# pcb.net
KiCad netlist of a schematic drawn in EAGLE
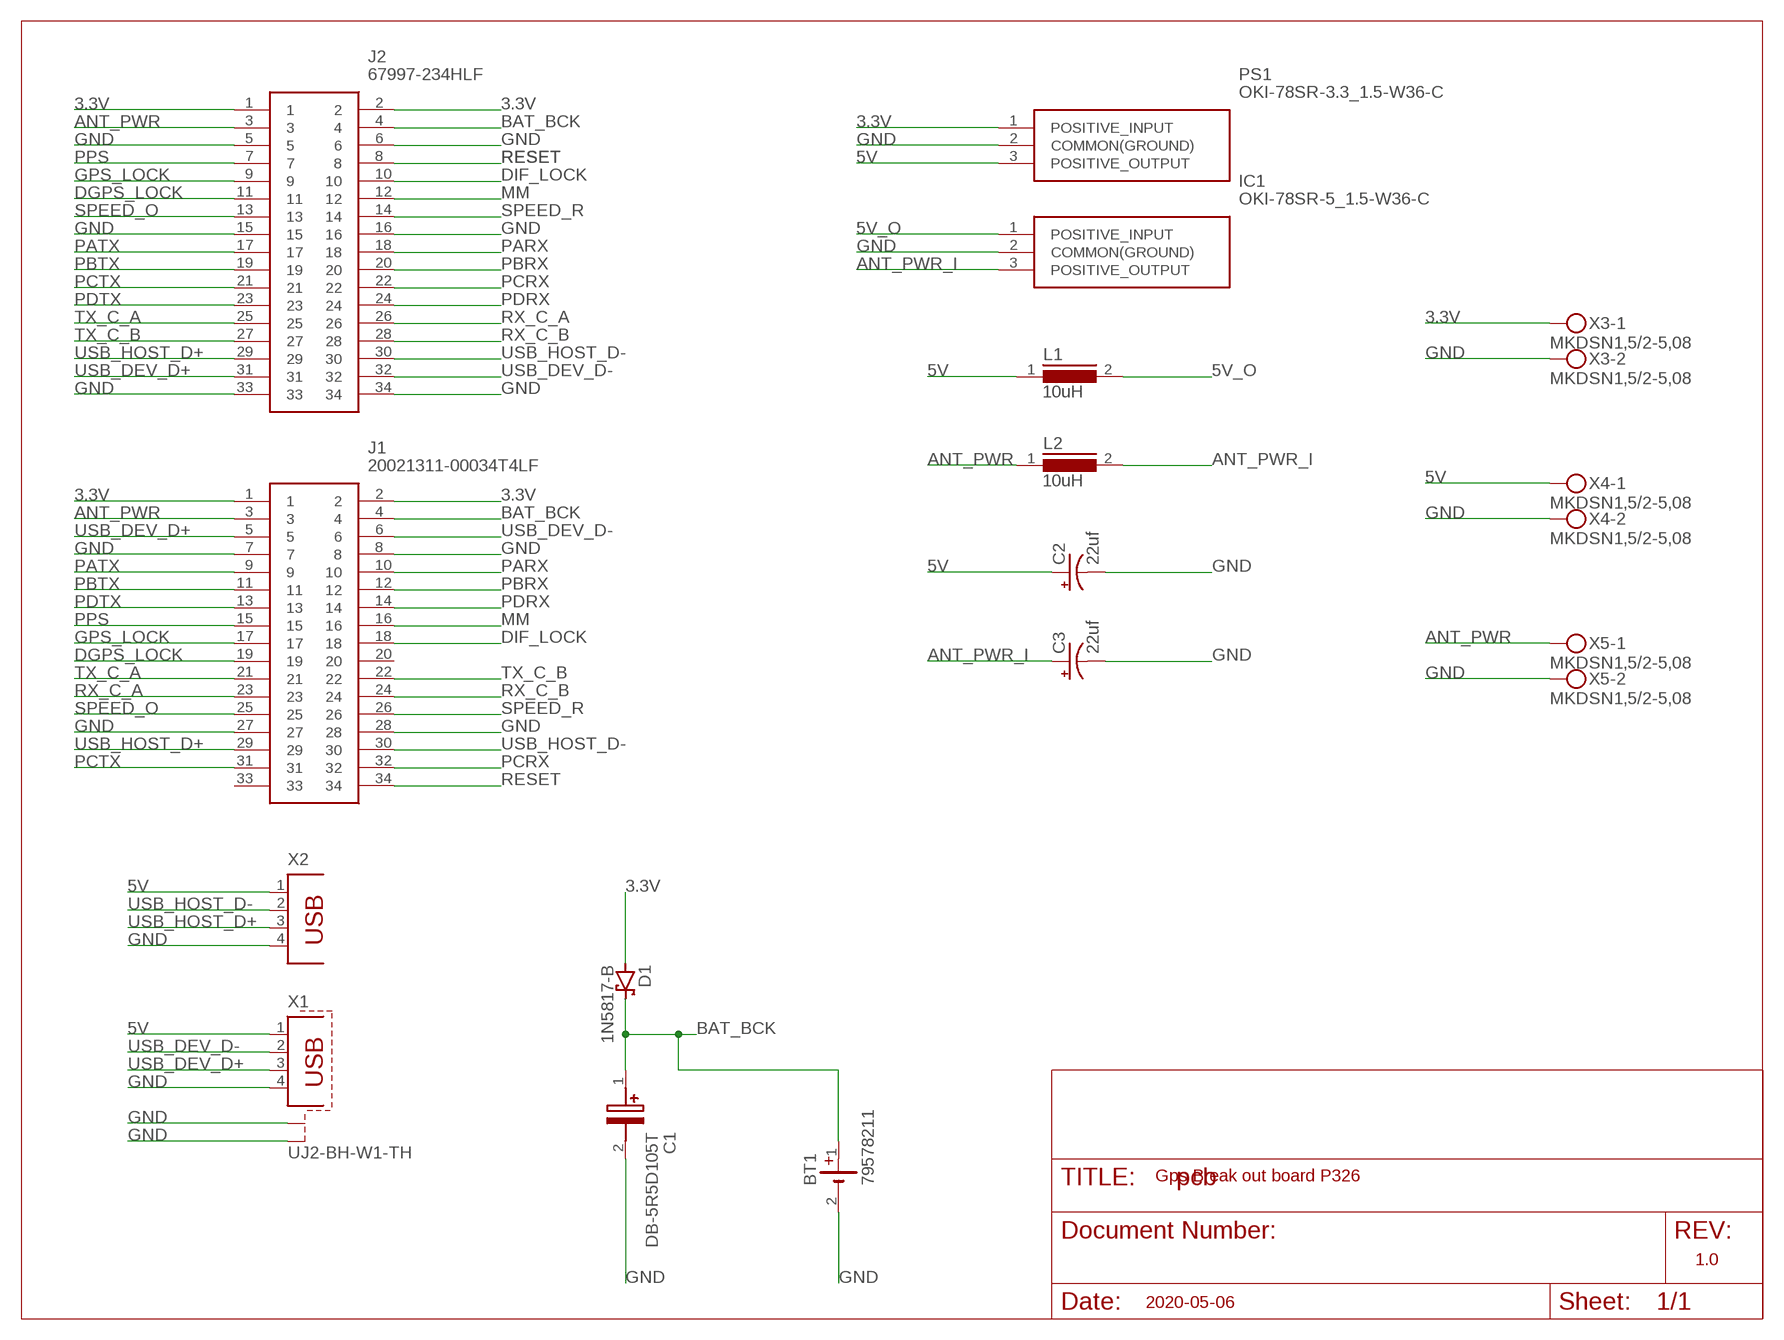
[diagram p0: schematic, sheet 1]

(export (version "E")
  (design (tool "Eeschema 10.0.6"))
  (components
    (comp (ref "BT1")
      (value "79578211")
      (footprint "eagle-import:79578211")
      (fields
        (field (name "DIGIKEY_PART_NO") "732-12330-ND")
        (field (name "MANUFACTURER") "Wurth Electronics Inc.")
        (field (name "CREATED_BY") "PCBLayout.com")
      )
      (libsource (lib "eagle-import") (part "79578211"))
    )
    (comp (ref "C1")
      (value "DB-5R5D105T")
      (footprint "eagle-import:CAPPRD500W130D2150H800")
      (fields (field (name "MOUSER_PART_NUMBER") "555-DB-5R5D105T"))
      (libsource (lib "eagle-import") (part "DB-5R5D105T"))
    )
    (comp (ref "C2")
      (value "22uf")
      (footprint "eagle-import:CAPPRD508W65D1000H1100B")
      (libsource (lib "eagle-import") (part "C-POL-USRADIAL-11MM-DIA_"))
    )
    (comp (ref "C3")
      (value "22uf")
      (footprint "eagle-import:CAPPRD508W65D1000H1100B")
      (libsource (lib "eagle-import") (part "C-POL-USRADIAL-11MM-DIA_"))
    )
    (comp (ref "D1")
      (value "1N5817-B")
      (footprint "eagle-import:DO41-7.6")
      (libsource (lib "eagle-import") (part "1N5817-B"))
    )
    (comp (ref "IC1")
      (value "OKI-78SR-5_1.5-W36-C")
      (footprint "eagle-import:OKI-78SR")
      (fields
        (field (name "MANUFACTURER_PART_NUMBER") "OKI-78SR-5/1.5-W36-C")
        (field (name "MOUSER_PART_NUMBER") "580-OKI78SR5/1.5W36C")
        (field (name "RS_PART_NUMBER") "7962132P")
      )
      (libsource (lib "eagle-import") (part "OKI-78SR-5_1.5-W36-C"))
    )
    (comp (ref "J1")
      (value "20021311-00034T4LF")
      (footprint "eagle-import:SFMC11701LDK")
      (fields
        (field (name "MANUFACTURER_PART_NUMBER") "SFMC-117-01-L-D-K")
        (field (name "MOUSER_PART_NUMBER") "200-SFMC11701LDK")
        (field (name "MANUFACTURER_NAME") "Amphenol ICC (FCI)")
        (field (name "MANUFACTURER_PART_NUMBER_1") "20021311-00034T4LF")
        (field (name "MOUSER_PART_NUMBER_1") "649-221311-00034T4LF")
        (field (name "MOUSER_PRICE-STOCK") "https://www.mouser.ca/ProductDetail/Amphenol-FCI/20021311-00034T4LF?qs=%2Fha2pyFaduhY7txd7xCZH4MnoZVHG9D20IyDq2KsCOnVLlItFYWmroWGFWusbTUh")
      )
      (libsource (lib "eagle-import") (part "SFMC-117-01-L-D-K"))
    )
    (comp (ref "J2")
      (value "67997-234HLF")
      (footprint "eagle-import:HDRV34W64P254_2X17_4318X495X83")
      (fields
        (field (name "MANUFACTURER_PART_NUMBER") "TSW-117-07-L-D")
        (field (name "MOUSER_PART_NUMBER") "200-TSW11707LD")
        (field (name "RS_PART_NUMBER") "1802714P")
        (field (name "MANUFACTURER_NAME") "Amphenol ICC (FCI)")
        (field (name "MANUFACTURER_PART_NUMBER_1") "67997-234HLF")
        (field (name "MOUSER_PART_NUMBER_1") "649-67997-234HLF")
        (field (name "MOUSER_PRICE-STOCK") "https://www.mouser.ca/ProductDetail/Amphenol-FCI/67997-234HLF?qs=%2Fha2pyFaduho4QXapRmeXGuJyHmXXipd3LGGQJh2eTsVKLqIuO2D5A%3D%3D")
      )
      (libsource (lib "eagle-import") (part "TSW-117-07-L-D"))
    )
    (comp (ref "L1")
      (value "10uH")
      (footprint "eagle-import:82114R")
      (libsource (lib "eagle-import") (part "82114R"))
    )
    (comp (ref "L2")
      (value "10uH")
      (footprint "eagle-import:82114R")
      (libsource (lib "eagle-import") (part "82114R"))
    )
    (comp (ref "PS1")
      (value "OKI-78SR-3.3_1.5-W36-C")
      (footprint "eagle-import:OKI-78SR")
      (fields
        (field (name "MANUFACTURER_PART_NUMBER") "OKI-78SR-5/1.5-W36-C")
        (field (name "MOUSER_PART_NUMBER") "580-OKI78SR5/1.5W36C")
        (field (name "RS_PART_NUMBER") "7962132P")
      )
      (libsource (lib "eagle-import") (part "OKI-78SR-5_1.5-W36-C"))
    )
    (comp (ref "X1")
      (value "UJ2-BH-W1-TH")
      (footprint "eagle-import:PN61729-S")
      (libsource (lib "eagle-import") (part "PN61729-S"))
    )
    (comp (ref "X2")
      (value "PN87520")
      (footprint "eagle-import:PN87520")
      (libsource (lib "eagle-import") (part "PN87520"))
    )
    (comp (ref "X3")
      (value "MKDSN1,5/2-5,08")
      (footprint "eagle-import:MKDSN1,5_2-5,08")
      (libsource (lib "eagle-import") (part "MKDSN1,5/2-5,08"))
    )
    (comp (ref "X4")
      (value "MKDSN1,5/2-5,08")
      (footprint "eagle-import:MKDSN1,5_2-5,08")
      (libsource (lib "eagle-import") (part "MKDSN1,5/2-5,08"))
    )
    (comp (ref "X5")
      (value "MKDSN1,5/2-5,08")
      (footprint "eagle-import:MKDSN1,5_2-5,08")
      (libsource (lib "eagle-import") (part "MKDSN1,5/2-5,08"))
    )
  )
  (nets
    (net (code "1") (name "/3.3V") (class "Default")
      (node (ref "D1") (pin "A") (pinfunction "A_A") (pintype "passive"))
      (node (ref "J1") (pin "1") (pinfunction "1_1") (pintype "bidirectional"))
      (node (ref "J1") (pin "2") (pinfunction "2_2") (pintype "bidirectional"))
      (node (ref "J2") (pin "1") (pinfunction "1_1") (pintype "bidirectional"))
      (node (ref "J2") (pin "2") (pinfunction "2_2") (pintype "bidirectional"))
      (node (ref "PS1") (pin "1") (pinfunction "POSITIVE_INPUT_1") (pintype "bidirectional"))
      (node (ref "X3") (pin "1") (pinfunction "KL_1") (pintype "passive"))
    )
    (net (code "2") (name "/5V") (class "Default")
      (node (ref "C2") (pin "1") (pinfunction "+_1") (pintype "passive"))
      (node (ref "L1") (pin "1") (pinfunction "1_1") (pintype "passive"))
      (node (ref "PS1") (pin "3") (pinfunction "POSITIVE_OUTPUT_3") (pintype "bidirectional"))
      (node (ref "X1") (pin "1") (pinfunction "1_1") (pintype "passive"))
      (node (ref "X2") (pin "1") (pinfunction "1_1") (pintype "passive"))
      (node (ref "X4") (pin "1") (pinfunction "KL_1") (pintype "passive"))
    )
    (net (code "3") (name "/5V_O") (class "Default")
      (node (ref "IC1") (pin "1") (pinfunction "POSITIVE_INPUT_1") (pintype "bidirectional"))
      (node (ref "L1") (pin "2") (pinfunction "2_2") (pintype "passive"))
    )
    (net (code "4") (name "/ANT_PWR") (class "Default")
      (node (ref "J1") (pin "3") (pinfunction "3_3") (pintype "bidirectional"))
      (node (ref "J2") (pin "3") (pinfunction "3_3") (pintype "bidirectional"))
      (node (ref "L2") (pin "1") (pinfunction "1_1") (pintype "passive"))
      (node (ref "X5") (pin "1") (pinfunction "KL_1") (pintype "passive"))
    )
    (net (code "5") (name "/ANT_PWR_I") (class "Default")
      (node (ref "C3") (pin "1") (pinfunction "+_1") (pintype "passive"))
      (node (ref "IC1") (pin "3") (pinfunction "POSITIVE_OUTPUT_3") (pintype "bidirectional"))
      (node (ref "L2") (pin "2") (pinfunction "2_2") (pintype "passive"))
    )
    (net (code "6") (name "/BAT_BCK") (class "Default")
      (node (ref "BT1") (pin "1") (pinfunction "+_1") (pintype "passive"))
      (node (ref "C1") (pin "1") (pinfunction "+_1") (pintype "bidirectional"))
      (node (ref "D1") (pin "C") (pinfunction "C_C") (pintype "passive"))
      (node (ref "J1") (pin "4") (pinfunction "4_4") (pintype "bidirectional"))
      (node (ref "J2") (pin "4") (pinfunction "4_4") (pintype "bidirectional"))
    )
    (net (code "7") (name "/DGPS_LOCK") (class "Default")
      (node (ref "J1") (pin "19") (pinfunction "19_19") (pintype "bidirectional"))
      (node (ref "J2") (pin "11") (pinfunction "11_11") (pintype "bidirectional"))
    )
    (net (code "8") (name "/DIF_LOCK") (class "Default")
      (node (ref "J1") (pin "18") (pinfunction "18_18") (pintype "bidirectional"))
      (node (ref "J2") (pin "10") (pinfunction "10_10") (pintype "bidirectional"))
    )
    (net (code "9") (name "/GND") (class "Default")
      (node (ref "BT1") (pin "2") (pinfunction "-_2") (pintype "passive"))
      (node (ref "C1") (pin "2") (pinfunction "-_2") (pintype "bidirectional"))
      (node (ref "C2") (pin "2") (pinfunction "-_2") (pintype "passive"))
      (node (ref "C3") (pin "2") (pinfunction "-_2") (pintype "passive"))
      (node (ref "IC1") (pin "2") (pinfunction "COMMON(GROUND)_2") (pintype "bidirectional"))
      (node (ref "J1") (pin "27") (pinfunction "27_27") (pintype "bidirectional"))
      (node (ref "J1") (pin "28") (pinfunction "28_28") (pintype "bidirectional"))
      (node (ref "J1") (pin "7") (pinfunction "7_7") (pintype "bidirectional"))
      (node (ref "J1") (pin "8") (pinfunction "8_8") (pintype "bidirectional"))
      (node (ref "J2") (pin "15") (pinfunction "15_15") (pintype "bidirectional"))
      (node (ref "J2") (pin "16") (pinfunction "16_16") (pintype "bidirectional"))
      (node (ref "J2") (pin "33") (pinfunction "33_33") (pintype "bidirectional"))
      (node (ref "J2") (pin "34") (pinfunction "34_34") (pintype "bidirectional"))
      (node (ref "J2") (pin "5") (pinfunction "5_5") (pintype "bidirectional"))
      (node (ref "J2") (pin "6") (pinfunction "6_6") (pintype "bidirectional"))
      (node (ref "PS1") (pin "2") (pinfunction "COMMON(GROUND)_2") (pintype "bidirectional"))
      (node (ref "X1") (pin "4") (pinfunction "4_4") (pintype "passive"))
      (node (ref "X1") (pin "S1") (pinfunction "S1_S1") (pintype "passive"))
      (node (ref "X1") (pin "S2") (pinfunction "S2_S2") (pintype "passive"))
      (node (ref "X2") (pin "4") (pinfunction "4_4") (pintype "passive"))
      (node (ref "X3") (pin "2") (pinfunction "KL_2") (pintype "passive"))
      (node (ref "X4") (pin "2") (pinfunction "KL_2") (pintype "passive"))
      (node (ref "X5") (pin "2") (pinfunction "KL_2") (pintype "passive"))
    )
    (net (code "10") (name "/GPS_LOCK") (class "Default")
      (node (ref "J1") (pin "17") (pinfunction "17_17") (pintype "bidirectional"))
      (node (ref "J2") (pin "9") (pinfunction "9_9") (pintype "bidirectional"))
    )
    (net (code "11") (name "/MM") (class "Default")
      (node (ref "J1") (pin "16") (pinfunction "16_16") (pintype "bidirectional"))
      (node (ref "J2") (pin "12") (pinfunction "12_12") (pintype "bidirectional"))
    )
    (net (code "12") (name "/PARX") (class "Default")
      (node (ref "J1") (pin "10") (pinfunction "10_10") (pintype "bidirectional"))
      (node (ref "J2") (pin "18") (pinfunction "18_18") (pintype "bidirectional"))
    )
    (net (code "13") (name "/PATX") (class "Default")
      (node (ref "J1") (pin "9") (pinfunction "9_9") (pintype "bidirectional"))
      (node (ref "J2") (pin "17") (pinfunction "17_17") (pintype "bidirectional"))
    )
    (net (code "14") (name "/PBRX") (class "Default")
      (node (ref "J1") (pin "12") (pinfunction "12_12") (pintype "bidirectional"))
      (node (ref "J2") (pin "20") (pinfunction "20_20") (pintype "bidirectional"))
    )
    (net (code "15") (name "/PBTX") (class "Default")
      (node (ref "J1") (pin "11") (pinfunction "11_11") (pintype "bidirectional"))
      (node (ref "J2") (pin "19") (pinfunction "19_19") (pintype "bidirectional"))
    )
    (net (code "16") (name "/PCRX") (class "Default")
      (node (ref "J1") (pin "32") (pinfunction "32_32") (pintype "bidirectional"))
      (node (ref "J2") (pin "22") (pinfunction "22_22") (pintype "bidirectional"))
    )
    (net (code "17") (name "/PCTX") (class "Default")
      (node (ref "J1") (pin "31") (pinfunction "31_31") (pintype "bidirectional"))
      (node (ref "J2") (pin "21") (pinfunction "21_21") (pintype "bidirectional"))
    )
    (net (code "18") (name "/PDRX") (class "Default")
      (node (ref "J1") (pin "14") (pinfunction "14_14") (pintype "bidirectional"))
      (node (ref "J2") (pin "24") (pinfunction "24_24") (pintype "bidirectional"))
    )
    (net (code "19") (name "/PDTX") (class "Default")
      (node (ref "J1") (pin "13") (pinfunction "13_13") (pintype "bidirectional"))
      (node (ref "J2") (pin "23") (pinfunction "23_23") (pintype "bidirectional"))
    )
    (net (code "20") (name "/PPS") (class "Default")
      (node (ref "J1") (pin "15") (pinfunction "15_15") (pintype "bidirectional"))
      (node (ref "J2") (pin "7") (pinfunction "7_7") (pintype "bidirectional"))
    )
    (net (code "21") (name "/RESET") (class "Default")
      (node (ref "J1") (pin "34") (pinfunction "34_34") (pintype "bidirectional"))
      (node (ref "J2") (pin "8") (pinfunction "8_8") (pintype "bidirectional"))
    )
    (net (code "22") (name "/RX_C_A") (class "Default")
      (node (ref "J1") (pin "23") (pinfunction "23_23") (pintype "bidirectional"))
      (node (ref "J2") (pin "26") (pinfunction "26_26") (pintype "bidirectional"))
    )
    (net (code "23") (name "/RX_C_B") (class "Default")
      (node (ref "J1") (pin "24") (pinfunction "24_24") (pintype "bidirectional"))
      (node (ref "J2") (pin "28") (pinfunction "28_28") (pintype "bidirectional"))
    )
    (net (code "24") (name "/SPEED_O") (class "Default")
      (node (ref "J1") (pin "25") (pinfunction "25_25") (pintype "bidirectional"))
      (node (ref "J2") (pin "13") (pinfunction "13_13") (pintype "bidirectional"))
    )
    (net (code "25") (name "/SPEED_R") (class "Default")
      (node (ref "J1") (pin "26") (pinfunction "26_26") (pintype "bidirectional"))
      (node (ref "J2") (pin "14") (pinfunction "14_14") (pintype "bidirectional"))
    )
    (net (code "26") (name "/TX_C_A") (class "Default")
      (node (ref "J1") (pin "21") (pinfunction "21_21") (pintype "bidirectional"))
      (node (ref "J2") (pin "25") (pinfunction "25_25") (pintype "bidirectional"))
    )
    (net (code "27") (name "/TX_C_B") (class "Default")
      (node (ref "J1") (pin "22") (pinfunction "22_22") (pintype "bidirectional"))
      (node (ref "J2") (pin "27") (pinfunction "27_27") (pintype "bidirectional"))
    )
    (net (code "28") (name "/USB_DEV_D+") (class "Default")
      (node (ref "J1") (pin "5") (pinfunction "5_5") (pintype "bidirectional"))
      (node (ref "J2") (pin "31") (pinfunction "31_31") (pintype "bidirectional"))
      (node (ref "X1") (pin "3") (pinfunction "3_3") (pintype "passive"))
    )
    (net (code "29") (name "/USB_DEV_D-") (class "Default")
      (node (ref "J1") (pin "6") (pinfunction "6_6") (pintype "bidirectional"))
      (node (ref "J2") (pin "32") (pinfunction "32_32") (pintype "bidirectional"))
      (node (ref "X1") (pin "2") (pinfunction "2_2") (pintype "passive"))
    )
    (net (code "30") (name "/USB_HOST_D+") (class "Default")
      (node (ref "J1") (pin "29") (pinfunction "29_29") (pintype "bidirectional"))
      (node (ref "J2") (pin "29") (pinfunction "29_29") (pintype "bidirectional"))
      (node (ref "X2") (pin "3") (pinfunction "3_3") (pintype "passive"))
    )
    (net (code "31") (name "/USB_HOST_D-") (class "Default")
      (node (ref "J1") (pin "30") (pinfunction "30_30") (pintype "bidirectional"))
      (node (ref "J2") (pin "30") (pinfunction "30_30") (pintype "bidirectional"))
      (node (ref "X2") (pin "2") (pinfunction "2_2") (pintype "passive"))
    )
    (net (code "32") (name "unconnected-(J1-Pad20)") (class "Default")
      (node (ref "J1") (pin "20") (pinfunction "20_20") (pintype "bidirectional"))
    )
    (net (code "33") (name "unconnected-(J1-Pad33)") (class "Default")
      (node (ref "J1") (pin "33") (pinfunction "33_33") (pintype "bidirectional"))
    )
  )
)
